# brakelight.net
KiCad netlist of a schematic drawn in EAGLE
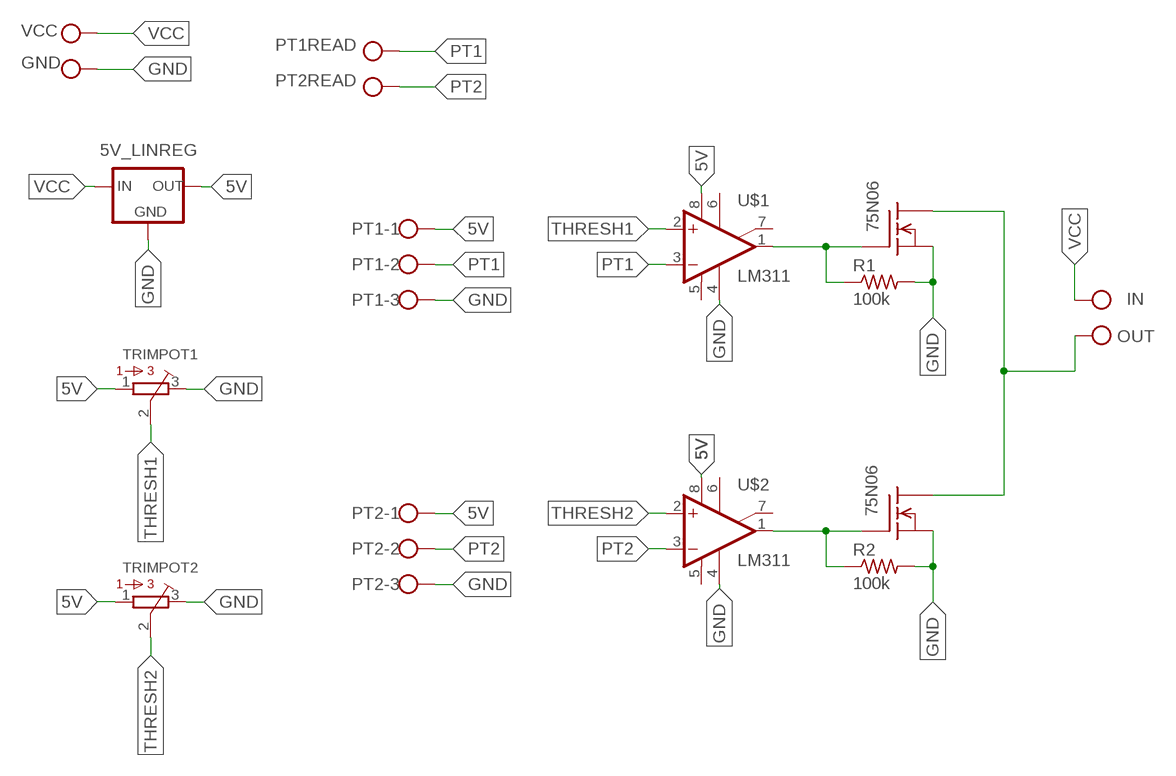
[diagram p0: schematic, sheet 1]

(export (version "E")
  (design (tool "Eeschema 10.0.6"))
  (components
    (comp (ref "5V_LINREG")
      (value "78XXL")
      (footprint "eagle-import:78XXL")
      (libsource (lib "eagle-import") (part "78XXL"))
    )
    (comp (ref "BRAKELIGHT")
      (value "W237-102")
      (footprint "eagle-import:W237-102")
      (fields (field (name "MPN") "237-102"))
      (libsource (lib "eagle-import") (part "W237-102"))
    )
    (comp (ref "INO_READ")
      (value "W237-102")
      (footprint "eagle-import:W237-102")
      (fields (field (name "MPN") "237-102"))
      (libsource (lib "eagle-import") (part "W237-102"))
    )
    (comp (ref "LIPO_CONN")
      (value "W237-102")
      (footprint "eagle-import:W237-102")
      (fields (field (name "MPN") "237-102"))
      (libsource (lib "eagle-import") (part "W237-102"))
    )
    (comp (ref "PT1")
      (value "W237-103")
      (footprint "eagle-import:W237-103")
      (fields (field (name "MPN") "237-103"))
      (libsource (lib "eagle-import") (part "W237-103"))
    )
    (comp (ref "PT2")
      (value "W237-103")
      (footprint "eagle-import:W237-103")
      (fields (field (name "MPN") "237-103"))
      (libsource (lib "eagle-import") (part "W237-103"))
    )
    (comp (ref "Q1")
      (value "75N06")
      (footprint "eagle-import:TO220")
      (libsource (lib "eagle-import") (part "SUP75N06-08"))
    )
    (comp (ref "Q2")
      (value "75N06")
      (footprint "eagle-import:TO220")
      (libsource (lib "eagle-import") (part "SUP75N06-08"))
    )
    (comp (ref "R1")
      (value "100k")
      (footprint "eagle-import:0204_7")
      (libsource (lib "eagle-import") (part "R-US_0204/7"))
    )
    (comp (ref "R2")
      (value "100k")
      (footprint "eagle-import:0204_7")
      (libsource (lib "eagle-import") (part "R-US_0204/7"))
    )
    (comp (ref "TRIMPOT1")
      (value "3386-Y")
      (footprint "eagle-import:3386Y")
      (libsource (lib "eagle-import") (part "3386-Y"))
    )
    (comp (ref "TRIMPOT2")
      (value "3386-Y")
      (footprint "eagle-import:3386Y")
      (libsource (lib "eagle-import") (part "3386-Y"))
    )
    (comp (ref "U$1")
      (value "LM311")
      (footprint "eagle-import:DIL08")
      (libsource (lib "eagle-import") (part "LM311"))
    )
    (comp (ref "U$2")
      (value "LM311")
      (footprint "eagle-import:DIL08")
      (libsource (lib "eagle-import") (part "LM311"))
    )
  )
  (nets
    (net (code "1") (name "5V") (class "Default")
      (node (ref "5V_LINREG") (pin "OUT") (pinfunction "OUT_OUT") (pintype "passive"))
      (node (ref "PT1") (pin "1") (pinfunction "KL_1") (pintype "passive"))
      (node (ref "PT2") (pin "1") (pinfunction "KL_1") (pintype "passive"))
      (node (ref "TRIMPOT1") (pin "1") (pinfunction "1_1") (pintype "passive"))
      (node (ref "TRIMPOT2") (pin "1") (pinfunction "1_1") (pintype "passive"))
      (node (ref "U$1") (pin "8") (pinfunction "V+_8") (pintype "power_in"))
      (node (ref "U$2") (pin "8") (pinfunction "V+_8") (pintype "power_in"))
    )
    (net (code "2") (name "GND") (class "Default")
      (node (ref "5V_LINREG") (pin "GND") (pinfunction "GND_GND") (pintype "input"))
      (node (ref "LIPO_CONN") (pin "2") (pinfunction "KL_2") (pintype "passive"))
      (node (ref "PT1") (pin "3") (pinfunction "KL_3") (pintype "passive"))
      (node (ref "PT2") (pin "3") (pinfunction "KL_3") (pintype "passive"))
      (node (ref "Q1") (pin "3") (pinfunction "S_3") (pintype "passive"))
      (node (ref "Q2") (pin "3") (pinfunction "S_3") (pintype "passive"))
      (node (ref "R1") (pin "2") (pinfunction "2_2") (pintype "passive"))
      (node (ref "R2") (pin "2") (pinfunction "2_2") (pintype "passive"))
      (node (ref "TRIMPOT1") (pin "3") (pinfunction "3_3") (pintype "passive"))
      (node (ref "TRIMPOT2") (pin "3") (pinfunction "3_3") (pintype "passive"))
      (node (ref "U$1") (pin "4") (pinfunction "GND_4") (pintype "passive"))
      (node (ref "U$2") (pin "4") (pinfunction "GND_4") (pintype "passive"))
    )
    (net (code "3") (name "Net-(BRAKELIGHTB-KL)") (class "Default")
      (node (ref "BRAKELIGHT") (pin "2") (pinfunction "KL_2") (pintype "passive"))
      (node (ref "Q1") (pin "2") (pinfunction "D_2") (pintype "passive"))
      (node (ref "Q2") (pin "2") (pinfunction "D_2") (pintype "passive"))
    )
    (net (code "4") (name "Net-(Q1-G)") (class "Default")
      (node (ref "Q1") (pin "1") (pinfunction "G_1") (pintype "passive"))
      (node (ref "R1") (pin "1") (pinfunction "1_1") (pintype "passive"))
      (node (ref "U$1") (pin "1") (pinfunction "OUT_1") (pintype "output"))
    )
    (net (code "5") (name "Net-(Q2-G)") (class "Default")
      (node (ref "Q2") (pin "1") (pinfunction "G_1") (pintype "passive"))
      (node (ref "R2") (pin "1") (pinfunction "1_1") (pintype "passive"))
      (node (ref "U$2") (pin "1") (pinfunction "OUT_1") (pintype "output"))
    )
    (net (code "6") (name "PT1") (class "Default")
      (node (ref "INO_READ") (pin "1") (pinfunction "KL_1") (pintype "passive"))
      (node (ref "PT1") (pin "2") (pinfunction "KL_2") (pintype "passive"))
      (node (ref "U$1") (pin "3") (pinfunction "-IN_3") (pintype "input"))
    )
    (net (code "7") (name "PT2") (class "Default")
      (node (ref "INO_READ") (pin "2") (pinfunction "KL_2") (pintype "passive"))
      (node (ref "PT2") (pin "2") (pinfunction "KL_2") (pintype "passive"))
      (node (ref "U$2") (pin "3") (pinfunction "-IN_3") (pintype "input"))
    )
    (net (code "8") (name "THRESH1") (class "Default")
      (node (ref "TRIMPOT1") (pin "2") (pinfunction "2_2") (pintype "passive"))
      (node (ref "U$1") (pin "2") (pinfunction "+IN_2") (pintype "input"))
    )
    (net (code "9") (name "THRESH2") (class "Default")
      (node (ref "TRIMPOT2") (pin "2") (pinfunction "2_2") (pintype "passive"))
      (node (ref "U$2") (pin "2") (pinfunction "+IN_2") (pintype "input"))
    )
    (net (code "10") (name "VCC") (class "Default")
      (node (ref "5V_LINREG") (pin "IN") (pinfunction "IN_IN") (pintype "input"))
      (node (ref "BRAKELIGHT") (pin "1") (pinfunction "KL_1") (pintype "passive"))
      (node (ref "LIPO_CONN") (pin "1") (pinfunction "KL_1") (pintype "passive"))
    )
    (net (code "11") (name "unconnected-(U$1-BAL-Pad5)") (class "Default")
      (node (ref "U$1") (pin "5") (pinfunction "BAL_5") (pintype "bidirectional"))
    )
    (net (code "12") (name "unconnected-(U$1-BAL{slash}STRB-Pad6)") (class "Default")
      (node (ref "U$1") (pin "6") (pinfunction "BAL/STRB_6") (pintype "bidirectional"))
    )
    (net (code "13") (name "unconnected-(U$1-COL_OUT-Pad7)") (class "Default")
      (node (ref "U$1") (pin "7") (pinfunction "COL_OUT_7") (pintype "input"))
    )
    (net (code "14") (name "unconnected-(U$2-BAL-Pad5)") (class "Default")
      (node (ref "U$2") (pin "5") (pinfunction "BAL_5") (pintype "bidirectional"))
    )
    (net (code "15") (name "unconnected-(U$2-BAL{slash}STRB-Pad6)") (class "Default")
      (node (ref "U$2") (pin "6") (pinfunction "BAL/STRB_6") (pintype "bidirectional"))
    )
    (net (code "16") (name "unconnected-(U$2-COL_OUT-Pad7)") (class "Default")
      (node (ref "U$2") (pin "7") (pinfunction "COL_OUT_7") (pintype "input"))
    )
  )
)
